# MCU.net
KiCad netlist of a schematic drawn in Altium Designer
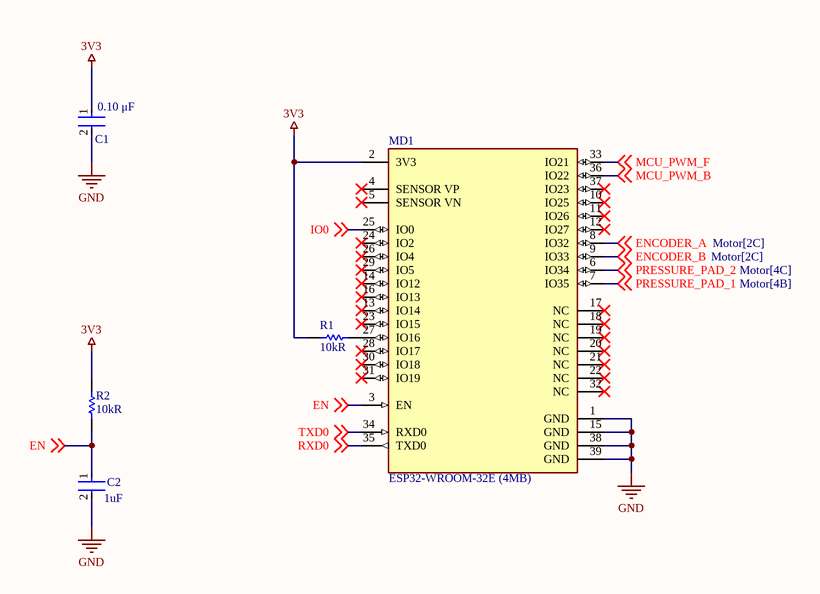
[diagram p0: MCU.SchDoc]

(export (version "E")
  (design (tool "Eeschema 10.0.6"))
  (components
    (comp (ref "C1")
      (value "0.10 μF")
      (footprint "FP-C1206C-EB-MFG")
      (description "CAP CER 0.1UF 100V X7R 1206")
      (fields
        (field (name "TOLERANCE") "0.1")
        (field (name "OCTOPART") "https://octopart.com/c1206c104k1ractu-kemet-89521")
      )
      (libsource (lib "Altium Content Vault") (part "b4654b650e69147ec39a6b967a45e02"))
    )
    (comp (ref "C2")
      (value "CL21B105KOFNNNE")
      (footprint "FP-CL21-IPC_A")
      (description "CL21 Series 0805 1uF 16V ±10% Tolerance X7R Multilayer Ceramic Chip Capacitor")
      (fields
        (field (name "CAPACITANCE") "1uF")
        (field (name "TOLERANCE") "10%")
        (field (name "VOLTAGE") "16V")
      )
      (libsource (lib "Altium Content Vault") (part "b4654b650e69147ec39a6b967a45e02"))
    )
    (comp (ref "MD1")
      (value "ESP32-WROOM-32E (4MB)")
      (footprint "FP-ESP32-WROOM-32E_4MB-MFG")
      (description "RX TXRX MOD WIFI TRACE ANT SMD")
      (libsource (lib "Altium Content Vault") (part "7f842c3463a9561e2f6f9fdcd687e0f"))
    )
    (comp (ref "R1")
      (value "10kR")
      (footprint "RESC2013X60X35NL10T20")
      (description "Chip Resistor, 10 KOhm, +/- 1%, 0.125 W, -55 to 155 degC, 0805 (2012 Metric), RoHS, Tape and Reel")
      (fields
        (field (name "MANUFACTURER") "Yageo")
        (field (name "MANUFACTURER PART NUMBER") "RC0805FR-0710KL")
      )
      (libsource (lib "Altium Content Vault") (part "RES-2"))
    )
    (comp (ref "R2")
      (value "10kR")
      (footprint "RESC2013X60X35NL10T20")
      (description "Chip Resistor, 10 KOhm, +/- 1%, 0.125 W, -55 to 155 degC, 0805 (2012 Metric), RoHS, Tape and Reel")
      (fields
        (field (name "MANUFACTURER") "Yageo")
        (field (name "MANUFACTURER PART NUMBER") "RC0805FR-0710KL")
      )
      (libsource (lib "Altium Content Vault") (part "RES-2"))
    )
  )
  (nets
    (net (code "1") (name "3V3") (class "Default")
      (node (ref "C1") (pin "1") (pinfunction "1_1") (pintype "passive"))
      (node (ref "MD1") (pin "2") (pinfunction "3V3_2") (pintype "power_in"))
      (node (ref "R1") (pin "2") (pinfunction "2_2") (pintype "passive"))
      (node (ref "R2") (pin "1") (pinfunction "1_1") (pintype "passive"))
    )
    (net (code "2") (name "EN") (class "Default")
      (node (ref "C2") (pin "1") (pinfunction "1_1") (pintype "passive"))
      (node (ref "MD1") (pin "3") (pinfunction "EN_3") (pintype "input"))
      (node (ref "R2") (pin "2") (pinfunction "2_2") (pintype "passive"))
    )
    (net (code "3") (name "ENCODER_A") (class "Default")
      (node (ref "MD1") (pin "8") (pinfunction "IO32_8") (pintype "bidirectional"))
    )
    (net (code "4") (name "ENCODER_B") (class "Default")
      (node (ref "MD1") (pin "9") (pinfunction "IO33_9") (pintype "bidirectional"))
    )
    (net (code "5") (name "GND") (class "Default")
      (node (ref "C1") (pin "2") (pinfunction "2_2") (pintype "passive"))
      (node (ref "C2") (pin "2") (pinfunction "2_2") (pintype "passive"))
      (node (ref "MD1") (pin "1") (pinfunction "GND_1") (pintype "power_in"))
      (node (ref "MD1") (pin "15") (pinfunction "GND_15") (pintype "power_in"))
      (node (ref "MD1") (pin "38") (pinfunction "GND_38") (pintype "power_in"))
      (node (ref "MD1") (pin "39") (pinfunction "GND_39") (pintype "power_in"))
    )
    (net (code "6") (name "IO0") (class "Default")
      (node (ref "MD1") (pin "25") (pinfunction "IO0_25") (pintype "bidirectional"))
    )
    (net (code "7") (name "MCU_PWM_B") (class "Default")
      (node (ref "MD1") (pin "36") (pinfunction "IO22_36") (pintype "bidirectional"))
    )
    (net (code "8") (name "MCU_PWM_F") (class "Default")
      (node (ref "MD1") (pin "33") (pinfunction "IO21_33") (pintype "bidirectional"))
    )
    (net (code "9") (name "Net-(MD1-IO16)") (class "Default")
      (node (ref "MD1") (pin "27") (pinfunction "IO16_27") (pintype "bidirectional"))
      (node (ref "R1") (pin "1") (pinfunction "1_1") (pintype "passive"))
    )
    (net (code "10") (name "PRESSURE_PAD_1") (class "Default")
      (node (ref "MD1") (pin "7") (pinfunction "IO35_7") (pintype "bidirectional"))
    )
    (net (code "11") (name "PRESSURE_PAD_2") (class "Default")
      (node (ref "MD1") (pin "6") (pinfunction "IO34_6") (pintype "bidirectional"))
    )
    (net (code "12") (name "RXD0") (class "Default")
      (node (ref "MD1") (pin "35") (pinfunction "TXD0_35") (pintype "output"))
    )
    (net (code "13") (name "TXD0") (class "Default")
      (node (ref "MD1") (pin "34") (pinfunction "RXD0_34") (pintype "input"))
    )
    (net (code "14") (name "unconnected-(MD1-IO2-Pad24)") (class "Default")
      (node (ref "MD1") (pin "24") (pinfunction "IO2_24") (pintype "bidirectional+no_connect"))
    )
    (net (code "15") (name "unconnected-(MD1-IO4-Pad26)") (class "Default")
      (node (ref "MD1") (pin "26") (pinfunction "IO4_26") (pintype "bidirectional+no_connect"))
    )
    (net (code "16") (name "unconnected-(MD1-IO5-Pad29)") (class "Default")
      (node (ref "MD1") (pin "29") (pinfunction "IO5_29") (pintype "bidirectional+no_connect"))
    )
    (net (code "17") (name "unconnected-(MD1-IO12-Pad14)") (class "Default")
      (node (ref "MD1") (pin "14") (pinfunction "IO12_14") (pintype "bidirectional+no_connect"))
    )
    (net (code "18") (name "unconnected-(MD1-IO13-Pad16)") (class "Default")
      (node (ref "MD1") (pin "16") (pinfunction "IO13_16") (pintype "bidirectional+no_connect"))
    )
    (net (code "19") (name "unconnected-(MD1-IO14-Pad13)") (class "Default")
      (node (ref "MD1") (pin "13") (pinfunction "IO14_13") (pintype "bidirectional+no_connect"))
    )
    (net (code "20") (name "unconnected-(MD1-IO15-Pad23)") (class "Default")
      (node (ref "MD1") (pin "23") (pinfunction "IO15_23") (pintype "bidirectional+no_connect"))
    )
    (net (code "21") (name "unconnected-(MD1-IO17-Pad28)") (class "Default")
      (node (ref "MD1") (pin "28") (pinfunction "IO17_28") (pintype "bidirectional+no_connect"))
    )
    (net (code "22") (name "unconnected-(MD1-IO18-Pad30)") (class "Default")
      (node (ref "MD1") (pin "30") (pinfunction "IO18_30") (pintype "bidirectional+no_connect"))
    )
    (net (code "23") (name "unconnected-(MD1-IO19-Pad31)") (class "Default")
      (node (ref "MD1") (pin "31") (pinfunction "IO19_31") (pintype "bidirectional+no_connect"))
    )
    (net (code "24") (name "unconnected-(MD1-IO23-Pad37)") (class "Default")
      (node (ref "MD1") (pin "37") (pinfunction "IO23_37") (pintype "bidirectional+no_connect"))
    )
    (net (code "25") (name "unconnected-(MD1-IO25-Pad10)") (class "Default")
      (node (ref "MD1") (pin "10") (pinfunction "IO25_10") (pintype "bidirectional+no_connect"))
    )
    (net (code "26") (name "unconnected-(MD1-IO26-Pad11)") (class "Default")
      (node (ref "MD1") (pin "11") (pinfunction "IO26_11") (pintype "bidirectional+no_connect"))
    )
    (net (code "27") (name "unconnected-(MD1-IO27-Pad12)") (class "Default")
      (node (ref "MD1") (pin "12") (pinfunction "IO27_12") (pintype "bidirectional+no_connect"))
    )
    (net (code "28") (name "unconnected-(MD1-NC-Pad17)") (class "Default")
      (node (ref "MD1") (pin "17") (pinfunction "NC_17") (pintype "passive+no_connect"))
    )
    (net (code "29") (name "unconnected-(MD1-NC-Pad18)") (class "Default")
      (node (ref "MD1") (pin "18") (pinfunction "NC_18") (pintype "passive+no_connect"))
    )
    (net (code "30") (name "unconnected-(MD1-NC-Pad19)") (class "Default")
      (node (ref "MD1") (pin "19") (pinfunction "NC_19") (pintype "passive+no_connect"))
    )
    (net (code "31") (name "unconnected-(MD1-NC-Pad20)") (class "Default")
      (node (ref "MD1") (pin "20") (pinfunction "NC_20") (pintype "passive+no_connect"))
    )
    (net (code "32") (name "unconnected-(MD1-NC-Pad21)") (class "Default")
      (node (ref "MD1") (pin "21") (pinfunction "NC_21") (pintype "passive+no_connect"))
    )
    (net (code "33") (name "unconnected-(MD1-NC-Pad22)") (class "Default")
      (node (ref "MD1") (pin "22") (pinfunction "NC_22") (pintype "passive+no_connect"))
    )
    (net (code "34") (name "unconnected-(MD1-NC-Pad32)") (class "Default")
      (node (ref "MD1") (pin "32") (pinfunction "NC_32") (pintype "passive+no_connect"))
    )
    (net (code "35") (name "unconnected-(MD1-SENSOR_VN-Pad5)") (class "Default")
      (node (ref "MD1") (pin "5") (pinfunction "SENSOR_VN_5") (pintype "passive+no_connect"))
    )
    (net (code "36") (name "unconnected-(MD1-SENSOR_VP-Pad4)") (class "Default")
      (node (ref "MD1") (pin "4") (pinfunction "SENSOR_VP_4") (pintype "passive+no_connect"))
    )
  )
)
